# audio-amp-max98365.net
KiCad netlist of a schematic drawn in EAGLE
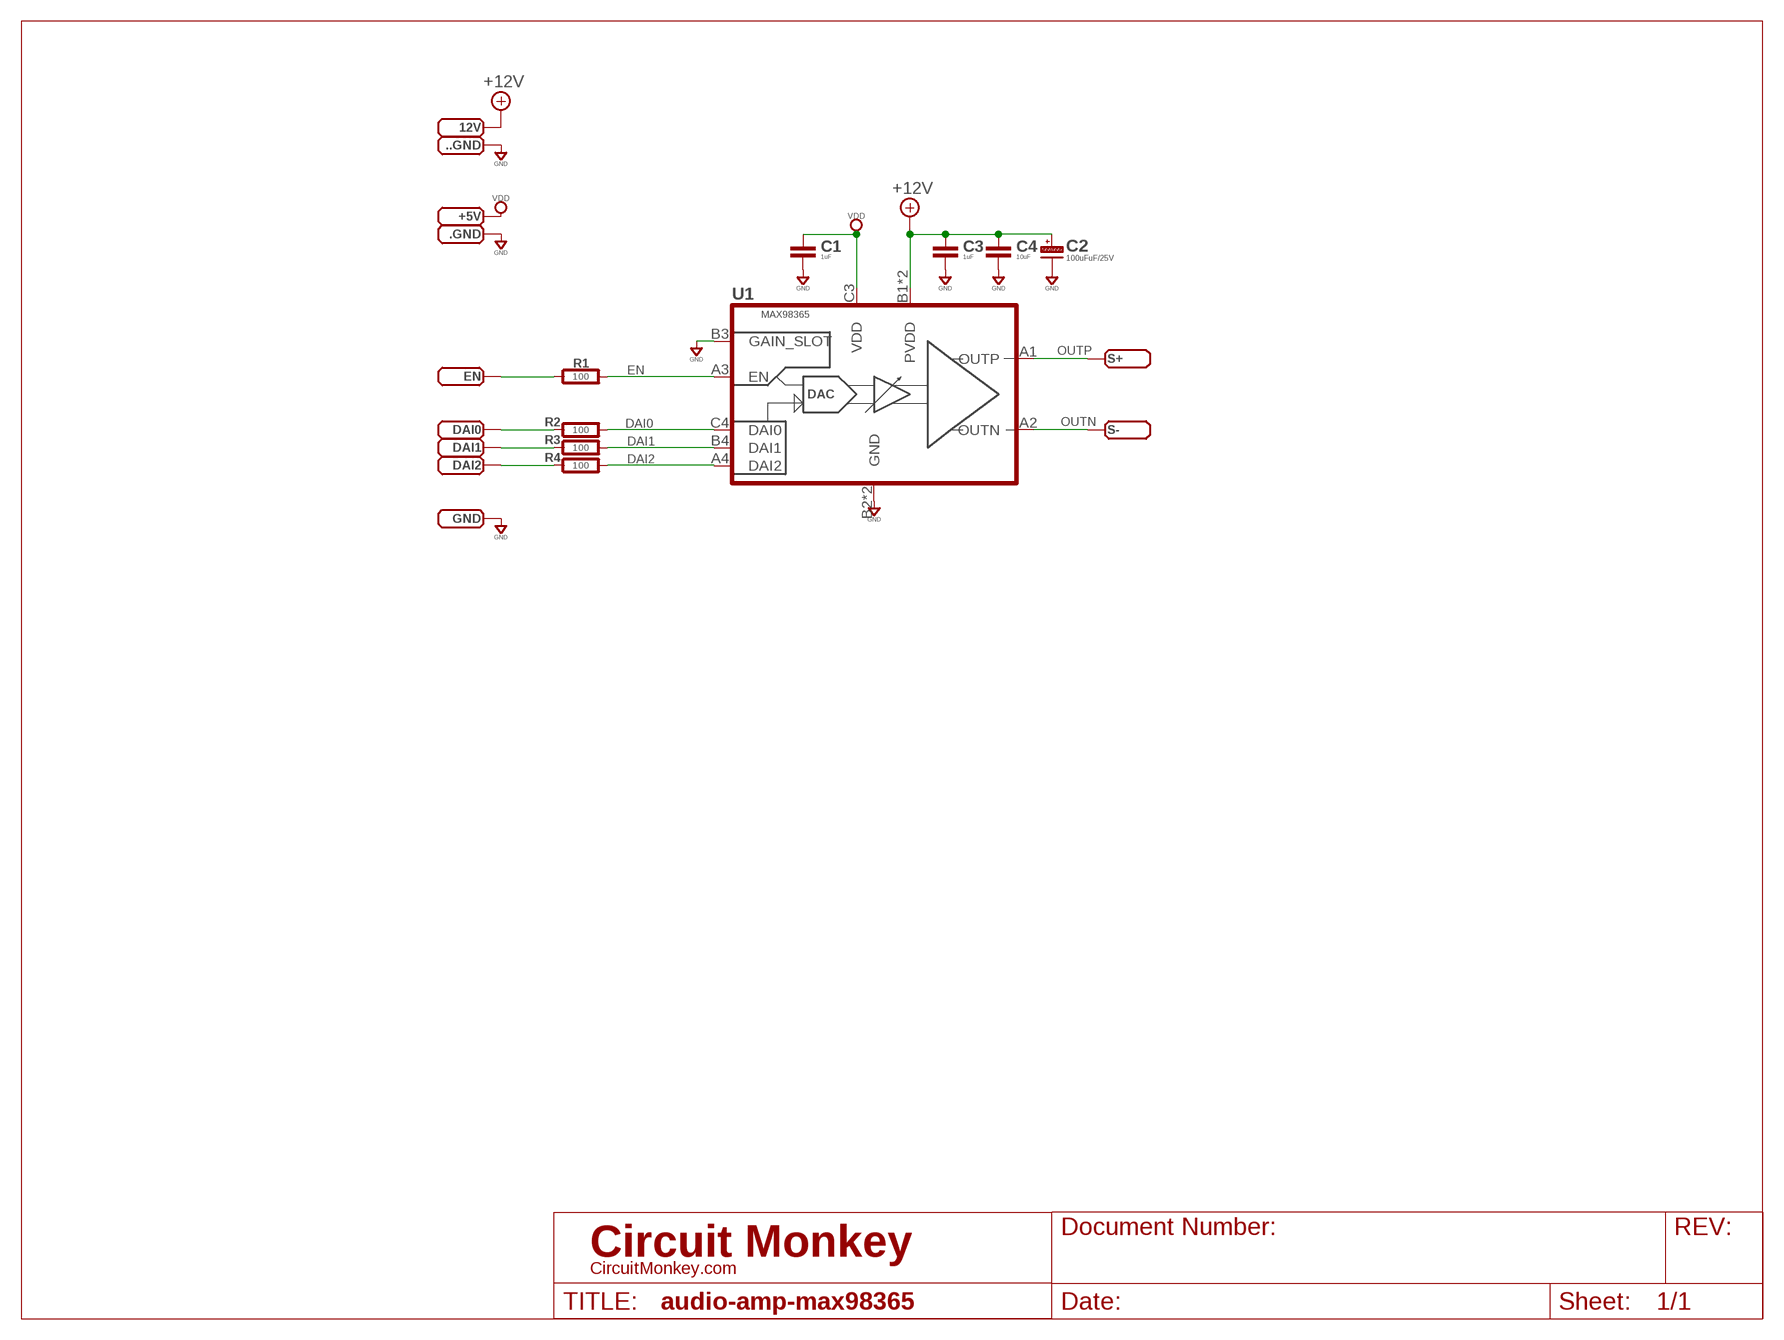
[diagram p0: schematic, sheet 1]

(export (version "E")
  (design (tool "Eeschema 10.0.6"))
  (components
    (comp (ref "+5V")
      (value "PADSMD-070X070")
      (footprint "eagle-import:SMD-070MIL")
      (libsource (lib "eagle-import") (part "PADSMD-070X070"))
    )
    (comp (ref "..GND")
      (value "PADSMD-070X070")
      (footprint "eagle-import:SMD-070MIL")
      (libsource (lib "eagle-import") (part "PADSMD-070X070"))
    )
    (comp (ref ".GND")
      (value "PADSMD-070X070")
      (footprint "eagle-import:SMD-070MIL")
      (libsource (lib "eagle-import") (part "PADSMD-070X070"))
    )
    (comp (ref "12V")
      (value "PADSMD-070X070")
      (footprint "eagle-import:SMD-070MIL")
      (libsource (lib "eagle-import") (part "PADSMD-070X070"))
    )
    (comp (ref "C1")
      (value "1uF")
      (footprint "eagle-import:0603-CAP")
      (libsource (lib "eagle-import") (part "CAPACITOR0603"))
    )
    (comp (ref "C2")
      (value "100uFuF/25V")
      (footprint "eagle-import:CAP_ALUM_SMT_6.3")
      (libsource (lib "eagle-import") (part "CAPACITOR_POL-ALUM-SMT-6.3"))
    )
    (comp (ref "C3")
      (value "1uF")
      (footprint "eagle-import:0603-CAP")
      (libsource (lib "eagle-import") (part "CAPACITOR0603"))
    )
    (comp (ref "C4")
      (value "10uF")
      (footprint "eagle-import:0603-CAP")
      (libsource (lib "eagle-import") (part "CAPACITOR0603"))
    )
    (comp (ref "DAI0")
      (value "PADSMD-070X070")
      (footprint "eagle-import:SMD-070MIL")
      (libsource (lib "eagle-import") (part "PADSMD-070X070"))
    )
    (comp (ref "DAI1")
      (value "PADSMD-070X070")
      (footprint "eagle-import:SMD-070MIL")
      (libsource (lib "eagle-import") (part "PADSMD-070X070"))
    )
    (comp (ref "DAI2")
      (value "PADSMD-070X070")
      (footprint "eagle-import:SMD-070MIL")
      (libsource (lib "eagle-import") (part "PADSMD-070X070"))
    )
    (comp (ref "EN")
      (value "PADSMD-070X070")
      (footprint "eagle-import:SMD-070MIL")
      (libsource (lib "eagle-import") (part "PADSMD-070X070"))
    )
    (comp (ref "GND")
      (value "PADSMD-070X070")
      (footprint "eagle-import:SMD-070MIL")
      (libsource (lib "eagle-import") (part "PADSMD-070X070"))
    )
    (comp (ref "R1")
      (value "100")
      (footprint "eagle-import:0603-RES")
      (libsource (lib "eagle-import") (part "RESISTOR0603"))
    )
    (comp (ref "R2")
      (value "100")
      (footprint "eagle-import:0603-RES")
      (libsource (lib "eagle-import") (part "RESISTOR0603"))
    )
    (comp (ref "R3")
      (value "100")
      (footprint "eagle-import:0603-RES")
      (libsource (lib "eagle-import") (part "RESISTOR0603"))
    )
    (comp (ref "R4")
      (value "100")
      (footprint "eagle-import:0603-RES")
      (libsource (lib "eagle-import") (part "RESISTOR0603"))
    )
    (comp (ref "S+")
      (value "PADSMD-100X100")
      (footprint "eagle-import:SMD-100X100")
      (libsource (lib "eagle-import") (part "PADSMD-100X100"))
    )
    (comp (ref "S-")
      (value "PADSMD-100X100")
      (footprint "eagle-import:SMD-100X100")
      (libsource (lib "eagle-import") (part "PADSMD-100X100"))
    )
    (comp (ref "U1")
      (value "MAX98365")
      (footprint "eagle-import:12WLP")
      (fields (field (name "MFR") "Maxim") (field (name "MPN") "MAX98365A/C"))
      (libsource (lib "eagle-import") (part "MAX98365"))
    )
  )
  (nets
    (net (code "1") (name "+12V") (class "Default")
      (node (ref "12V") (pin "1") (pinfunction "PAD_1") (pintype "bidirectional"))
      (node (ref "C2") (pin "+") (pinfunction "P_+") (pintype "bidirectional"))
      (node (ref "C3") (pin "1") (pinfunction "1_1") (pintype "passive"))
      (node (ref "C4") (pin "1") (pinfunction "1_1") (pintype "passive"))
      (node (ref "U1") (pin "B1") (pinfunction "PVDD_B1") (pintype "bidirectional"))
      (node (ref "U1") (pin "C1") (pinfunction "PVDD_C1") (pintype "bidirectional"))
    )
    (net (code "2") (name "/DAI0") (class "Default")
      (node (ref "R2") (pin "2") (pinfunction "2_2") (pintype "passive"))
      (node (ref "U1") (pin "C4") (pinfunction "DAI0_C4") (pintype "bidirectional"))
    )
    (net (code "3") (name "/DAI1") (class "Default")
      (node (ref "R3") (pin "2") (pinfunction "2_2") (pintype "passive"))
      (node (ref "U1") (pin "B4") (pinfunction "DAI1_B4") (pintype "bidirectional"))
    )
    (net (code "4") (name "/DAI2") (class "Default")
      (node (ref "R4") (pin "2") (pinfunction "2_2") (pintype "passive"))
      (node (ref "U1") (pin "A4") (pinfunction "DAI2_A4") (pintype "bidirectional"))
    )
    (net (code "5") (name "/EN") (class "Default")
      (node (ref "R1") (pin "2") (pinfunction "2_2") (pintype "passive"))
      (node (ref "U1") (pin "A3") (pinfunction "EN_A3") (pintype "bidirectional"))
    )
    (net (code "6") (name "/OUTN") (class "Default")
      (node (ref "S-") (pin "PAD") (pinfunction "PAD_PAD") (pintype "bidirectional"))
      (node (ref "U1") (pin "A2") (pinfunction "OUTN_A2") (pintype "bidirectional"))
    )
    (net (code "7") (name "/OUTP") (class "Default")
      (node (ref "S+") (pin "PAD") (pinfunction "PAD_PAD") (pintype "bidirectional"))
      (node (ref "U1") (pin "A1") (pinfunction "OUTP_A1") (pintype "bidirectional"))
    )
    (net (code "8") (name "GND") (class "Default")
      (node (ref "..GND") (pin "1") (pinfunction "PAD_1") (pintype "bidirectional"))
      (node (ref ".GND") (pin "1") (pinfunction "PAD_1") (pintype "bidirectional"))
      (node (ref "C1") (pin "2") (pinfunction "2_2") (pintype "passive"))
      (node (ref "C2") (pin "-") (pinfunction "N_-") (pintype "bidirectional"))
      (node (ref "C3") (pin "2") (pinfunction "2_2") (pintype "passive"))
      (node (ref "C4") (pin "2") (pinfunction "2_2") (pintype "passive"))
      (node (ref "GND") (pin "1") (pinfunction "PAD_1") (pintype "bidirectional"))
      (node (ref "U1") (pin "B2") (pinfunction "GND_B2") (pintype "bidirectional"))
      (node (ref "U1") (pin "B3") (pinfunction "GAIN_SLOT_B3") (pintype "bidirectional"))
      (node (ref "U1") (pin "C2") (pinfunction "GND_C2") (pintype "bidirectional"))
    )
    (net (code "9") (name "Net-(DAI0-PAD)") (class "Default")
      (node (ref "DAI0") (pin "1") (pinfunction "PAD_1") (pintype "bidirectional"))
      (node (ref "R2") (pin "1") (pinfunction "1_1") (pintype "passive"))
    )
    (net (code "10") (name "Net-(DAI1-PAD)") (class "Default")
      (node (ref "DAI1") (pin "1") (pinfunction "PAD_1") (pintype "bidirectional"))
      (node (ref "R3") (pin "1") (pinfunction "1_1") (pintype "passive"))
    )
    (net (code "11") (name "Net-(DAI2-PAD)") (class "Default")
      (node (ref "DAI2") (pin "1") (pinfunction "PAD_1") (pintype "bidirectional"))
      (node (ref "R4") (pin "1") (pinfunction "1_1") (pintype "passive"))
    )
    (net (code "12") (name "Net-(EN-PAD)") (class "Default")
      (node (ref "EN") (pin "1") (pinfunction "PAD_1") (pintype "bidirectional"))
      (node (ref "R1") (pin "1") (pinfunction "1_1") (pintype "passive"))
    )
    (net (code "13") (name "VDD") (class "Default")
      (node (ref "+5V") (pin "1") (pinfunction "PAD_1") (pintype "bidirectional"))
      (node (ref "C1") (pin "1") (pinfunction "1_1") (pintype "passive"))
      (node (ref "U1") (pin "C3") (pinfunction "VDD_C3") (pintype "bidirectional"))
    )
  )
)
